# 5_MOTORES_DE_PASSO.net
KiCad netlist of a schematic drawn in Altium Designer
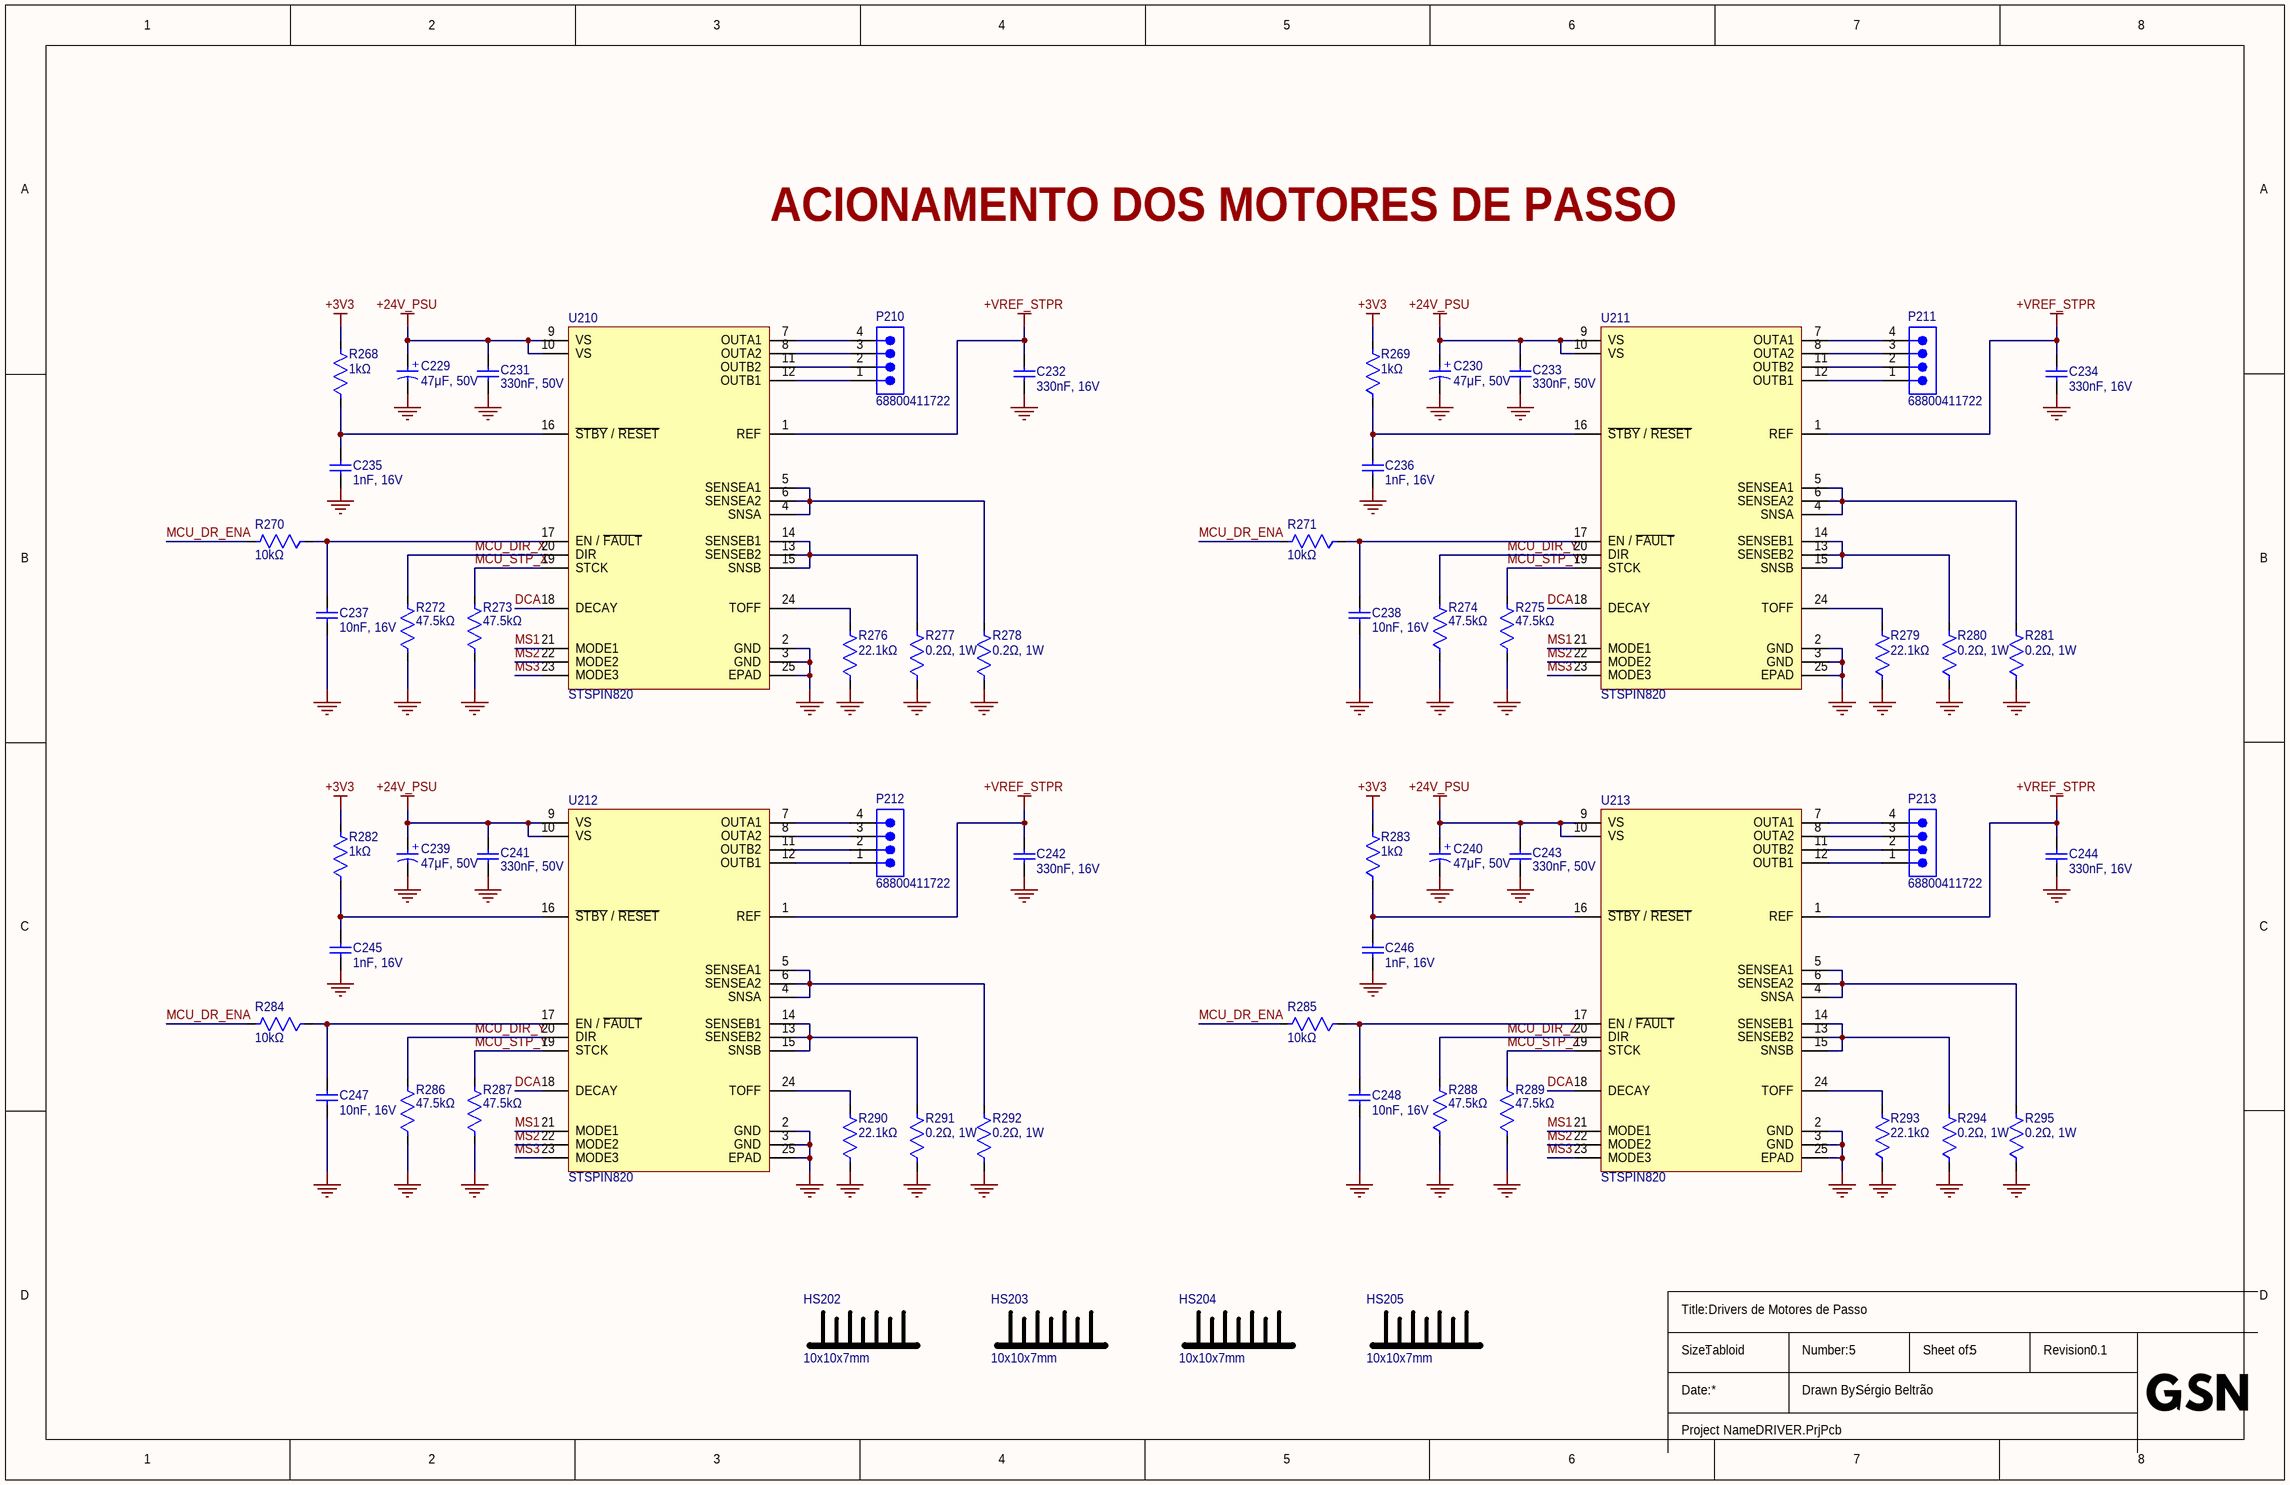
[diagram p0: 5_MOTORES_DE_PASSO.SchDoc]

(export (version "E")
  (design (tool "Eeschema 10.0.6"))
  (components
    (comp (ref "C229")
      (value "47μF, 50V")
      (footprint "WCAP-ASLI_D6.3H7.7")
      (description "WCAP-ASLI Aluminum Electrolytic Capacitor, V-Chip, SMT, 6.3mm x 7.7mm, 47μF, 50V")
      (fields
        (field (name "MANUFACTURER PART NUMBER") "865080645012")
        (field (name "MANUFACTURER") "Wurth Elektronik")
      )
      (libsource (lib "WE - Passive Components") (part "Capacitor_Polarized"))
    )
    (comp (ref "C230")
      (value "47μF, 50V")
      (footprint "WCAP-ASLI_D6.3H7.7")
      (description "WCAP-ASLI Aluminum Electrolytic Capacitor, V-Chip, SMT, 6.3mm x 7.7mm, 47μF, 50V")
      (fields
        (field (name "MANUFACTURER PART NUMBER") "865080645012")
        (field (name "MANUFACTURER") "Wurth Elektronik")
      )
      (libsource (lib "WE - Passive Components") (part "Capacitor_Polarized"))
    )
    (comp (ref "C231")
      (value "330nF, 50V")
      (footprint "WCAP-CSGP_0603_L1.6W0.8H0.8_Wave")
      (description "WCAP-CSGP Multilayer Ceramic Chip Capacitor, General Purpose, size 0603, 330nF, 50V")
      (fields
        (field (name "MANUFACTURER PART NUMBER") "885012206121")
        (field (name "MANUFACTURER") "Wurth Elektronik")
      )
      (libsource (lib "WE - Passive Components") (part "Capacitor_Non-Polarized"))
    )
    (comp (ref "C232")
      (value "330nF, 16V")
      (footprint "WCAP-CSGP_0603_L1.6W0.8H0.8_Wave")
      (description "WCAP-CSGP Multilayer Ceramic Chip Capacitor, General Purpose, size 0603, 330nF, 16V")
      (fields
        (field (name "MANUFACTURER PART NUMBER") "885012206049")
        (field (name "MANUFACTURER") "Wurth Elektronik")
      )
      (libsource (lib "WE - Passive Components") (part "Capacitor_Non-Polarized"))
    )
    (comp (ref "C233")
      (value "330nF, 50V")
      (footprint "WCAP-CSGP_0603_L1.6W0.8H0.8_Wave")
      (description "WCAP-CSGP Multilayer Ceramic Chip Capacitor, General Purpose, size 0603, 330nF, 50V")
      (fields
        (field (name "MANUFACTURER PART NUMBER") "885012206121")
        (field (name "MANUFACTURER") "Wurth Elektronik")
      )
      (libsource (lib "WE - Passive Components") (part "Capacitor_Non-Polarized"))
    )
    (comp (ref "C234")
      (value "330nF, 16V")
      (footprint "WCAP-CSGP_0603_L1.6W0.8H0.8_Wave")
      (description "WCAP-CSGP Multilayer Ceramic Chip Capacitor, General Purpose, size 0603, 330nF, 16V")
      (fields
        (field (name "MANUFACTURER PART NUMBER") "885012206049")
        (field (name "MANUFACTURER") "Wurth Elektronik")
      )
      (libsource (lib "WE - Passive Components") (part "Capacitor_Non-Polarized"))
    )
    (comp (ref "C235")
      (value "1nF, 16V")
      (footprint "WCAP-CSGP_0603_L1.6W0.8H0.8_Wave")
      (description "WCAP-CSGP Multilayer Ceramic Chip Capacitor, General Purpose, size 0603, 1nF, 16V")
      (fields
        (field (name "MANUFACTURER PART NUMBER") "885012206034")
        (field (name "MANUFACTURER") "Wurth Elektronik")
      )
      (libsource (lib "WE - Passive Components") (part "Capacitor_Non-Polarized"))
    )
    (comp (ref "C236")
      (value "1nF, 16V")
      (footprint "WCAP-CSGP_0603_L1.6W0.8H0.8_Wave")
      (description "WCAP-CSGP Multilayer Ceramic Chip Capacitor, General Purpose, size 0603, 1nF, 16V")
      (fields
        (field (name "MANUFACTURER PART NUMBER") "885012206034")
        (field (name "MANUFACTURER") "Wurth Elektronik")
      )
      (libsource (lib "WE - Passive Components") (part "Capacitor_Non-Polarized"))
    )
    (comp (ref "C237")
      (value "10nF, 16V")
      (footprint "WCAP-CSGP_0603_L1.6W0.8H0.8_Wave")
      (description "WCAP-CSGP Multilayer Ceramic Chip Capacitor, General Purpose, size 0603, 10nF, 16V")
      (fields
        (field (name "MANUFACTURER PART NUMBER") "885012206040")
        (field (name "MANUFACTURER") "Wurth Elektronik")
      )
      (libsource (lib "WE - Passive Components") (part "Capacitor_Non-Polarized"))
    )
    (comp (ref "C238")
      (value "10nF, 16V")
      (footprint "WCAP-CSGP_0603_L1.6W0.8H0.8_Wave")
      (description "WCAP-CSGP Multilayer Ceramic Chip Capacitor, General Purpose, size 0603, 10nF, 16V")
      (fields
        (field (name "MANUFACTURER PART NUMBER") "885012206040")
        (field (name "MANUFACTURER") "Wurth Elektronik")
      )
      (libsource (lib "WE - Passive Components") (part "Capacitor_Non-Polarized"))
    )
    (comp (ref "C239")
      (value "47μF, 50V")
      (footprint "WCAP-ASLI_D6.3H7.7")
      (description "WCAP-ASLI Aluminum Electrolytic Capacitor, V-Chip, SMT, 6.3mm x 7.7mm, 47μF, 50V")
      (fields
        (field (name "MANUFACTURER PART NUMBER") "865080645012")
        (field (name "MANUFACTURER") "Wurth Elektronik")
      )
      (libsource (lib "WE - Passive Components") (part "Capacitor_Polarized"))
    )
    (comp (ref "C240")
      (value "47μF, 50V")
      (footprint "WCAP-ASLI_D6.3H7.7")
      (description "WCAP-ASLI Aluminum Electrolytic Capacitor, V-Chip, SMT, 6.3mm x 7.7mm, 47μF, 50V")
      (fields
        (field (name "MANUFACTURER PART NUMBER") "865080645012")
        (field (name "MANUFACTURER") "Wurth Elektronik")
      )
      (libsource (lib "WE - Passive Components") (part "Capacitor_Polarized"))
    )
    (comp (ref "C241")
      (value "330nF, 50V")
      (footprint "WCAP-CSGP_0603_L1.6W0.8H0.8_Wave")
      (description "WCAP-CSGP Multilayer Ceramic Chip Capacitor, General Purpose, size 0603, 330nF, 50V")
      (fields
        (field (name "MANUFACTURER PART NUMBER") "885012206121")
        (field (name "MANUFACTURER") "Wurth Elektronik")
      )
      (libsource (lib "WE - Passive Components") (part "Capacitor_Non-Polarized"))
    )
    (comp (ref "C242")
      (value "330nF, 16V")
      (footprint "WCAP-CSGP_0603_L1.6W0.8H0.8_Wave")
      (description "WCAP-CSGP Multilayer Ceramic Chip Capacitor, General Purpose, size 0603, 330nF, 16V")
      (fields
        (field (name "MANUFACTURER PART NUMBER") "885012206049")
        (field (name "MANUFACTURER") "Wurth Elektronik")
      )
      (libsource (lib "WE - Passive Components") (part "Capacitor_Non-Polarized"))
    )
    (comp (ref "C243")
      (value "330nF, 50V")
      (footprint "WCAP-CSGP_0603_L1.6W0.8H0.8_Wave")
      (description "WCAP-CSGP Multilayer Ceramic Chip Capacitor, General Purpose, size 0603, 330nF, 50V")
      (fields
        (field (name "MANUFACTURER PART NUMBER") "885012206121")
        (field (name "MANUFACTURER") "Wurth Elektronik")
      )
      (libsource (lib "WE - Passive Components") (part "Capacitor_Non-Polarized"))
    )
    (comp (ref "C244")
      (value "330nF, 16V")
      (footprint "WCAP-CSGP_0603_L1.6W0.8H0.8_Wave")
      (description "WCAP-CSGP Multilayer Ceramic Chip Capacitor, General Purpose, size 0603, 330nF, 16V")
      (fields
        (field (name "MANUFACTURER PART NUMBER") "885012206049")
        (field (name "MANUFACTURER") "Wurth Elektronik")
      )
      (libsource (lib "WE - Passive Components") (part "Capacitor_Non-Polarized"))
    )
    (comp (ref "C245")
      (value "1nF, 16V")
      (footprint "WCAP-CSGP_0603_L1.6W0.8H0.8_Wave")
      (description "WCAP-CSGP Multilayer Ceramic Chip Capacitor, General Purpose, size 0603, 1nF, 16V")
      (fields
        (field (name "MANUFACTURER PART NUMBER") "885012206034")
        (field (name "MANUFACTURER") "Wurth Elektronik")
      )
      (libsource (lib "WE - Passive Components") (part "Capacitor_Non-Polarized"))
    )
    (comp (ref "C246")
      (value "1nF, 16V")
      (footprint "WCAP-CSGP_0603_L1.6W0.8H0.8_Wave")
      (description "WCAP-CSGP Multilayer Ceramic Chip Capacitor, General Purpose, size 0603, 1nF, 16V")
      (fields
        (field (name "MANUFACTURER PART NUMBER") "885012206034")
        (field (name "MANUFACTURER") "Wurth Elektronik")
      )
      (libsource (lib "WE - Passive Components") (part "Capacitor_Non-Polarized"))
    )
    (comp (ref "C247")
      (value "10nF, 16V")
      (footprint "WCAP-CSGP_0603_L1.6W0.8H0.8_Wave")
      (description "WCAP-CSGP Multilayer Ceramic Chip Capacitor, General Purpose, size 0603, 10nF, 16V")
      (fields
        (field (name "MANUFACTURER PART NUMBER") "885012206040")
        (field (name "MANUFACTURER") "Wurth Elektronik")
      )
      (libsource (lib "WE - Passive Components") (part "Capacitor_Non-Polarized"))
    )
    (comp (ref "C248")
      (value "10nF, 16V")
      (footprint "WCAP-CSGP_0603_L1.6W0.8H0.8_Wave")
      (description "WCAP-CSGP Multilayer Ceramic Chip Capacitor, General Purpose, size 0603, 10nF, 16V")
      (fields
        (field (name "MANUFACTURER PART NUMBER") "885012206040")
        (field (name "MANUFACTURER") "Wurth Elektronik")
      )
      (libsource (lib "WE - Passive Components") (part "Capacitor_Non-Polarized"))
    )
    (comp (ref "HS202")
      (value "10x10x7mm")
      (footprint "HEATSINK_10MM_10MM_7MM")
      (description "GENERIC HEATSINK 10X10X7MM")
      (fields (field (name "MANUFACTURER") "OEM") (field (name "MANUFACTURER PART NUMBER") "None"))
      (libsource (lib "Electro-Mechanical") (part "GENERIC-HEATSINK-10X10X7MM"))
    )
    (comp (ref "HS203")
      (value "10x10x7mm")
      (footprint "HEATSINK_10MM_10MM_7MM")
      (description "GENERIC HEATSINK 10X10X7MM")
      (fields (field (name "MANUFACTURER") "OEM") (field (name "MANUFACTURER PART NUMBER") "None"))
      (libsource (lib "Electro-Mechanical") (part "GENERIC-HEATSINK-10X10X7MM"))
    )
    (comp (ref "HS204")
      (value "10x10x7mm")
      (footprint "HEATSINK_10MM_10MM_7MM")
      (description "GENERIC HEATSINK 10X10X7MM")
      (fields (field (name "MANUFACTURER") "OEM") (field (name "MANUFACTURER PART NUMBER") "None"))
      (libsource (lib "Electro-Mechanical") (part "GENERIC-HEATSINK-10X10X7MM"))
    )
    (comp (ref "HS205")
      (value "10x10x7mm")
      (footprint "HEATSINK_10MM_10MM_7MM")
      (description "GENERIC HEATSINK 10X10X7MM")
      (fields (field (name "MANUFACTURER") "OEM") (field (name "MANUFACTURER PART NUMBER") "None"))
      (libsource (lib "Electro-Mechanical") (part "GENERIC-HEATSINK-10X10X7MM"))
    )
    (comp (ref "P210")
      (value "68800411722")
      (footprint "68800411722")
      (description "WR-WTB “J” Type THT Male Horizontal Shrouded Header, pitch 2.5 mm, 4 pins")
      (fields (field (name "MANUFACTURER") "Wurth Elektronik"))
      (libsource (lib "WE - Electromechanical Components") (part "Header_Male_1R_04P"))
    )
    (comp (ref "P211")
      (value "68800411722")
      (footprint "68800411722")
      (description "WR-WTB “J” Type THT Male Horizontal Shrouded Header, pitch 2.5 mm, 4 pins")
      (fields (field (name "MANUFACTURER") "Wurth Elektronik"))
      (libsource (lib "WE - Electromechanical Components") (part "Header_Male_1R_04P"))
    )
    (comp (ref "P212")
      (value "68800411722")
      (footprint "68800411722")
      (description "WR-WTB “J” Type THT Male Horizontal Shrouded Header, pitch 2.5 mm, 4 pins")
      (fields (field (name "MANUFACTURER") "Wurth Elektronik"))
      (libsource (lib "WE - Electromechanical Components") (part "Header_Male_1R_04P"))
    )
    (comp (ref "P213")
      (value "68800411722")
      (footprint "68800411722")
      (description "WR-WTB “J” Type THT Male Horizontal Shrouded Header, pitch 2.5 mm, 4 pins")
      (fields (field (name "MANUFACTURER") "Wurth Elektronik"))
      (libsource (lib "WE - Electromechanical Components") (part "Header_Male_1R_04P"))
    )
    (comp (ref "R268")
      (value "1kΩ")
      (footprint "0603-WAVE")
      (description "RES 1K OHM 1% 1/10W 0603")
      (fields
        (field (name "MANUFACTURER PART NUMBER") "RC0603FR-071KL")
        (field (name "MANUFACTURER") "Yageo Group")
      )
      (libsource (lib "Resistors-0603-E96-Yageo") (part "RC0603FR-071KL"))
    )
    (comp (ref "R269")
      (value "1kΩ")
      (footprint "0603-WAVE")
      (description "RES 1K OHM 1% 1/10W 0603")
      (fields
        (field (name "MANUFACTURER PART NUMBER") "RC0603FR-071KL")
        (field (name "MANUFACTURER") "Yageo Group")
      )
      (libsource (lib "Resistors-0603-E96-Yageo") (part "RC0603FR-071KL"))
    )
    (comp (ref "R270")
      (value "10kΩ")
      (footprint "0603-WAVE")
      (description "RES 10K OHM 1% 1/10W 0603")
      (fields
        (field (name "MANUFACTURER PART NUMBER") "RC0603FR-0710KL")
        (field (name "MANUFACTURER") "Yageo Group")
      )
      (libsource (lib "Resistors-0603-E96-Yageo") (part "RC0603FR-0710KL"))
    )
    (comp (ref "R271")
      (value "10kΩ")
      (footprint "0603-WAVE")
      (description "RES 10K OHM 1% 1/10W 0603")
      (fields
        (field (name "MANUFACTURER PART NUMBER") "RC0603FR-0710KL")
        (field (name "MANUFACTURER") "Yageo Group")
      )
      (libsource (lib "Resistors-0603-E96-Yageo") (part "RC0603FR-0710KL"))
    )
    (comp (ref "R272")
      (value "47.5kΩ")
      (footprint "0603-WAVE")
      (description "RES 47.5K OHM 1% 1/10W 0603")
      (fields
        (field (name "MANUFACTURER PART NUMBER") "RC0603FR-0747K5L")
        (field (name "MANUFACTURER") "Yageo Group")
      )
      (libsource (lib "Resistors-0603-E96-Yageo") (part "RC0603FR-0747K5L"))
    )
    (comp (ref "R273")
      (value "47.5kΩ")
      (footprint "0603-WAVE")
      (description "RES 47.5K OHM 1% 1/10W 0603")
      (fields
        (field (name "MANUFACTURER PART NUMBER") "RC0603FR-0747K5L")
        (field (name "MANUFACTURER") "Yageo Group")
      )
      (libsource (lib "Resistors-0603-E96-Yageo") (part "RC0603FR-0747K5L"))
    )
    (comp (ref "R274")
      (value "47.5kΩ")
      (footprint "0603-WAVE")
      (description "RES 47.5K OHM 1% 1/10W 0603")
      (fields
        (field (name "MANUFACTURER PART NUMBER") "RC0603FR-0747K5L")
        (field (name "MANUFACTURER") "Yageo Group")
      )
      (libsource (lib "Resistors-0603-E96-Yageo") (part "RC0603FR-0747K5L"))
    )
    (comp (ref "R275")
      (value "47.5kΩ")
      (footprint "0603-WAVE")
      (description "RES 47.5K OHM 1% 1/10W 0603")
      (fields
        (field (name "MANUFACTURER PART NUMBER") "RC0603FR-0747K5L")
        (field (name "MANUFACTURER") "Yageo Group")
      )
      (libsource (lib "Resistors-0603-E96-Yageo") (part "RC0603FR-0747K5L"))
    )
    (comp (ref "R276")
      (value "22.1kΩ")
      (footprint "0603-WAVE")
      (description "RES 22.1K OHM 1% 1/10W 0603")
      (fields
        (field (name "MANUFACTURER PART NUMBER") "RC0603FR-0722K1L")
        (field (name "MANUFACTURER") "Yageo Group")
      )
      (libsource (lib "Resistors-0603-E96-Yageo") (part "RC0603FR-0722K1L"))
    )
    (comp (ref "R277")
      (value "0.2Ω, 1W")
      (footprint "2512-WAVE")
      (description "RES 0.2 OHM 1% 1W 2512")
      (fields
        (field (name "MANUFACTURER") "Yageo Group")
        (field (name "MANUFACTURER PART NUMBER") "RL2512FK-070R2L")
      )
      (libsource (lib "Resistors-2512-Shunt") (part "RL2512FK-070R2L"))
    )
    (comp (ref "R278")
      (value "0.2Ω, 1W")
      (footprint "2512-WAVE")
      (description "RES 0.2 OHM 1% 1W 2512")
      (fields
        (field (name "MANUFACTURER") "Yageo Group")
        (field (name "MANUFACTURER PART NUMBER") "RL2512FK-070R2L")
      )
      (libsource (lib "Resistors-2512-Shunt") (part "RL2512FK-070R2L"))
    )
    (comp (ref "R279")
      (value "22.1kΩ")
      (footprint "0603-WAVE")
      (description "RES 22.1K OHM 1% 1/10W 0603")
      (fields
        (field (name "MANUFACTURER PART NUMBER") "RC0603FR-0722K1L")
        (field (name "MANUFACTURER") "Yageo Group")
      )
      (libsource (lib "Resistors-0603-E96-Yageo") (part "RC0603FR-0722K1L"))
    )
    (comp (ref "R280")
      (value "0.2Ω, 1W")
      (footprint "2512-WAVE")
      (description "RES 0.2 OHM 1% 1W 2512")
      (fields
        (field (name "MANUFACTURER") "Yageo Group")
        (field (name "MANUFACTURER PART NUMBER") "RL2512FK-070R2L")
      )
      (libsource (lib "Resistors-2512-Shunt") (part "RL2512FK-070R2L"))
    )
    (comp (ref "R281")
      (value "0.2Ω, 1W")
      (footprint "2512-WAVE")
      (description "RES 0.2 OHM 1% 1W 2512")
      (fields
        (field (name "MANUFACTURER") "Yageo Group")
        (field (name "MANUFACTURER PART NUMBER") "RL2512FK-070R2L")
      )
      (libsource (lib "Resistors-2512-Shunt") (part "RL2512FK-070R2L"))
    )
    (comp (ref "R282")
      (value "1kΩ")
      (footprint "0603-WAVE")
      (description "RES 1K OHM 1% 1/10W 0603")
      (fields
        (field (name "MANUFACTURER PART NUMBER") "RC0603FR-071KL")
        (field (name "MANUFACTURER") "Yageo Group")
      )
      (libsource (lib "Resistors-0603-E96-Yageo") (part "RC0603FR-071KL"))
    )
    (comp (ref "R283")
      (value "1kΩ")
      (footprint "0603-WAVE")
      (description "RES 1K OHM 1% 1/10W 0603")
      (fields
        (field (name "MANUFACTURER PART NUMBER") "RC0603FR-071KL")
        (field (name "MANUFACTURER") "Yageo Group")
      )
      (libsource (lib "Resistors-0603-E96-Yageo") (part "RC0603FR-071KL"))
    )
    (comp (ref "R284")
      (value "10kΩ")
      (footprint "0603-WAVE")
      (description "RES 10K OHM 1% 1/10W 0603")
      (fields
        (field (name "MANUFACTURER PART NUMBER") "RC0603FR-0710KL")
        (field (name "MANUFACTURER") "Yageo Group")
      )
      (libsource (lib "Resistors-0603-E96-Yageo") (part "RC0603FR-0710KL"))
    )
    (comp (ref "R285")
      (value "10kΩ")
      (footprint "0603-WAVE")
      (description "RES 10K OHM 1% 1/10W 0603")
      (fields
        (field (name "MANUFACTURER PART NUMBER") "RC0603FR-0710KL")
        (field (name "MANUFACTURER") "Yageo Group")
      )
      (libsource (lib "Resistors-0603-E96-Yageo") (part "RC0603FR-0710KL"))
    )
    (comp (ref "R286")
      (value "47.5kΩ")
      (footprint "0603-WAVE")
      (description "RES 47.5K OHM 1% 1/10W 0603")
      (fields
        (field (name "MANUFACTURER PART NUMBER") "RC0603FR-0747K5L")
        (field (name "MANUFACTURER") "Yageo Group")
      )
      (libsource (lib "Resistors-0603-E96-Yageo") (part "RC0603FR-0747K5L"))
    )
    (comp (ref "R287")
      (value "47.5kΩ")
      (footprint "0603-WAVE")
      (description "RES 47.5K OHM 1% 1/10W 0603")
      (fields
        (field (name "MANUFACTURER PART NUMBER") "RC0603FR-0747K5L")
        (field (name "MANUFACTURER") "Yageo Group")
      )
      (libsource (lib "Resistors-0603-E96-Yageo") (part "RC0603FR-0747K5L"))
    )
    (comp (ref "R288")
      (value "47.5kΩ")
      (footprint "0603-WAVE")
      (description "RES 47.5K OHM 1% 1/10W 0603")
      (fields
        (field (name "MANUFACTURER PART NUMBER") "RC0603FR-0747K5L")
        (field (name "MANUFACTURER") "Yageo Group")
      )
      (libsource (lib "Resistors-0603-E96-Yageo") (part "RC0603FR-0747K5L"))
    )
    (comp (ref "R289")
      (value "47.5kΩ")
      (footprint "0603-WAVE")
      (description "RES 47.5K OHM 1% 1/10W 0603")
      (fields
        (field (name "MANUFACTURER PART NUMBER") "RC0603FR-0747K5L")
        (field (name "MANUFACTURER") "Yageo Group")
      )
      (libsource (lib "Resistors-0603-E96-Yageo") (part "RC0603FR-0747K5L"))
    )
    (comp (ref "R290")
      (value "22.1kΩ")
      (footprint "0603-WAVE")
      (description "RES 22.1K OHM 1% 1/10W 0603")
      (fields
        (field (name "MANUFACTURER PART NUMBER") "RC0603FR-0722K1L")
        (field (name "MANUFACTURER") "Yageo Group")
      )
      (libsource (lib "Resistors-0603-E96-Yageo") (part "RC0603FR-0722K1L"))
    )
    (comp (ref "R291")
      (value "0.2Ω, 1W")
      (footprint "2512-WAVE")
      (description "RES 0.2 OHM 1% 1W 2512")
      (fields
        (field (name "MANUFACTURER") "Yageo Group")
        (field (name "MANUFACTURER PART NUMBER") "RL2512FK-070R2L")
      )
      (libsource (lib "Resistors-2512-Shunt") (part "RL2512FK-070R2L"))
    )
    (comp (ref "R292")
      (value "0.2Ω, 1W")
      (footprint "2512-WAVE")
      (description "RES 0.2 OHM 1% 1W 2512")
      (fields
        (field (name "MANUFACTURER") "Yageo Group")
        (field (name "MANUFACTURER PART NUMBER") "RL2512FK-070R2L")
      )
      (libsource (lib "Resistors-2512-Shunt") (part "RL2512FK-070R2L"))
    )
    (comp (ref "R293")
      (value "22.1kΩ")
      (footprint "0603-WAVE")
      (description "RES 22.1K OHM 1% 1/10W 0603")
      (fields
        (field (name "MANUFACTURER PART NUMBER") "RC0603FR-0722K1L")
        (field (name "MANUFACTURER") "Yageo Group")
      )
      (libsource (lib "Resistors-0603-E96-Yageo") (part "RC0603FR-0722K1L"))
    )
    (comp (ref "R294")
      (value "0.2Ω, 1W")
      (footprint "2512-WAVE")
      (description "RES 0.2 OHM 1% 1W 2512")
      (fields
        (field (name "MANUFACTURER") "Yageo Group")
        (field (name "MANUFACTURER PART NUMBER") "RL2512FK-070R2L")
      )
      (libsource (lib "Resistors-2512-Shunt") (part "RL2512FK-070R2L"))
    )
    (comp (ref "R295")
      (value "0.2Ω, 1W")
      (footprint "2512-WAVE")
      (description "RES 0.2 OHM 1% 1W 2512")
      (fields
        (field (name "MANUFACTURER") "Yageo Group")
        (field (name "MANUFACTURER PART NUMBER") "RL2512FK-070R2L")
      )
      (libsource (lib "Resistors-2512-Shunt") (part "RL2512FK-070R2L"))
    )
    (comp (ref "U210")
      (value "STSPIN820")
      (footprint "24-TQFPN")
      (description "IC MTR DRVR BIPLR 7-45V 24TFQFPN")
      (fields (field (name "MANUFACTURER") "STMicroelectronics"))
      (libsource (lib "Motor-Drivers") (part "STSPIN820"))
    )
    (comp (ref "U211")
      (value "STSPIN820")
      (footprint "24-TQFPN")
      (description "IC MTR DRVR BIPLR 7-45V 24TFQFPN")
      (fields (field (name "MANUFACTURER") "STMicroelectronics"))
      (libsource (lib "Motor-Drivers") (part "STSPIN820"))
    )
    (comp (ref "U212")
      (value "STSPIN820")
      (footprint "24-TQFPN")
      (description "IC MTR DRVR BIPLR 7-45V 24TFQFPN")
      (fields (field (name "MANUFACTURER") "STMicroelectronics"))
      (libsource (lib "Motor-Drivers") (part "STSPIN820"))
    )
    (comp (ref "U213")
      (value "STSPIN820")
      (footprint "24-TQFPN")
      (description "IC MTR DRVR BIPLR 7-45V 24TFQFPN")
      (fields (field (name "MANUFACTURER") "STMicroelectronics"))
      (libsource (lib "Motor-Drivers") (part "STSPIN820"))
    )
  )
  (nets
    (net (code "1") (name "+3V3") (class "Default")
      (node (ref "R268") (pin "2") (pinfunction "2_2") (pintype "passive"))
      (node (ref "R269") (pin "2") (pinfunction "2_2") (pintype "passive"))
      (node (ref "R282") (pin "2") (pinfunction "2_2") (pintype "passive"))
      (node (ref "R283") (pin "2") (pinfunction "2_2") (pintype "passive"))
    )
    (net (code "2") (name "+24V_PSU") (class "Default")
      (node (ref "C229") (pin "1") (pinfunction "P_1") (pintype "passive"))
      (node (ref "C230") (pin "1") (pinfunction "P_1") (pintype "passive"))
      (node (ref "C231") (pin "2") (pinfunction "2_2") (pintype "passive"))
      (node (ref "C233") (pin "2") (pinfunction "2_2") (pintype "passive"))
      (node (ref "C239") (pin "1") (pinfunction "P_1") (pintype "passive"))
      (node (ref "C240") (pin "1") (pinfunction "P_1") (pintype "passive"))
      (node (ref "C241") (pin "2") (pinfunction "2_2") (pintype "passive"))
      (node (ref "C243") (pin "2") (pinfunction "2_2") (pintype "passive"))
      (node (ref "U210") (pin "10") (pinfunction "VS_10") (pintype "passive"))
      (node (ref "U210") (pin "9") (pinfunction "VS_9") (pintype "passive"))
      (node (ref "U211") (pin "10") (pinfunction "VS_10") (pintype "passive"))
      (node (ref "U211") (pin "9") (pinfunction "VS_9") (pintype "passive"))
      (node (ref "U212") (pin "10") (pinfunction "VS_10") (pintype "passive"))
      (node (ref "U212") (pin "9") (pinfunction "VS_9") (pintype "passive"))
      (node (ref "U213") (pin "10") (pinfunction "VS_10") (pintype "passive"))
      (node (ref "U213") (pin "9") (pinfunction "VS_9") (pintype "passive"))
    )
    (net (code "3") (name "+VREF_STPR") (class "Default")
      (node (ref "C232") (pin "2") (pinfunction "2_2") (pintype "passive"))
      (node (ref "C234") (pin "2") (pinfunction "2_2") (pintype "passive"))
      (node (ref "C242") (pin "2") (pinfunction "2_2") (pintype "passive"))
      (node (ref "C244") (pin "2") (pinfunction "2_2") (pintype "passive"))
      (node (ref "U210") (pin "1") (pinfunction "REF_1") (pintype "passive"))
      (node (ref "U211") (pin "1") (pinfunction "REF_1") (pintype "passive"))
      (node (ref "U212") (pin "1") (pinfunction "REF_1") (pintype "passive"))
      (node (ref "U213") (pin "1") (pinfunction "REF_1") (pintype "passive"))
    )
    (net (code "4") (name "/DCA") (class "Default")
      (node (ref "U210") (pin "18") (pinfunction "DECAY_18") (pintype "passive"))
      (node (ref "U211") (pin "18") (pinfunction "DECAY_18") (pintype "passive"))
      (node (ref "U212") (pin "18") (pinfunction "DECAY_18") (pintype "passive"))
      (node (ref "U213") (pin "18") (pinfunction "DECAY_18") (pintype "passive"))
    )
    (net (code "5") (name "/MCU_DIR_X") (class "Default")
      (node (ref "R272") (pin "2") (pinfunction "2_2") (pintype "passive"))
      (node (ref "U210") (pin "20") (pinfunction "DIR_20") (pintype "passive"))
    )
    (net (code "6") (name "/MCU_DIR_Y") (class "Default")
      (node (ref "R274") (pin "2") (pinfunction "2_2") (pintype "passive"))
      (node (ref "R286") (pin "2") (pinfunction "2_2") (pintype "passive"))
      (node (ref "U211") (pin "20") (pinfunction "DIR_20") (pintype "passive"))
      (node (ref "U212") (pin "20") (pinfunction "DIR_20") (pintype "passive"))
    )
    (net (code "7") (name "/MCU_DIR_Z") (class "Default")
      (node (ref "R288") (pin "2") (pinfunction "2_2") (pintype "passive"))
      (node (ref "U213") (pin "20") (pinfunction "DIR_20") (pintype "passive"))
    )
    (net (code "8") (name "/MCU_DR_ENA") (class "Default")
      (node (ref "R270") (pin "2") (pinfunction "2_2") (pintype "passive"))
      (node (ref "R271") (pin "2") (pinfunction "2_2") (pintype "passive"))
      (node (ref "R284") (pin "2") (pinfunction "2_2") (pintype "passive"))
      (node (ref "R285") (pin "2") (pinfunction "2_2") (pintype "passive"))
    )
    (net (code "9") (name "/MCU_STP_X") (class "Default")
      (node (ref "R273") (pin "2") (pinfunction "2_2") (pintype "passive"))
      (node (ref "U210") (pin "19") (pinfunction "STCK_19") (pintype "passive"))
    )
    (net (code "10") (name "/MCU_STP_Y") (class "Default")
      (node (ref "R275") (pin "2") (pinfunction "2_2") (pintype "passive"))
      (node (ref "R287") (pin "2") (pinfunction "2_2") (pintype "passive"))
      (node (ref "U211") (pin "19") (pinfunction "STCK_19") (pintype "passive"))
      (node (ref "U212") (pin "19") (pinfunction "STCK_19") (pintype "passive"))
    )
    (net (code "11") (name "/MCU_STP_Z") (class "Default")
      (node (ref "R289") (pin "2") (pinfunction "2_2") (pintype "passive"))
      (node (ref "U213") (pin "19") (pinfunction "STCK_19") (pintype "passive"))
    )
    (net (code "12") (name "/MS1") (class "Default")
      (node (ref "U210") (pin "21") (pinfunction "MODE1_21") (pintype "passive"))
      (node (ref "U211") (pin "21") (pinfunction "MODE1_21") (pintype "passive"))
      (node (ref "U212") (pin "21") (pinfunction "MODE1_21") (pintype "passive"))
      (node (ref "U213") (pin "21") (pinfunction "MODE1_21") (pintype "passive"))
    )
    (net (code "13") (name "/MS2") (class "Default")
      (node (ref "U210") (pin "22") (pinfunction "MODE2_22") (pintype "passive"))
      (node (ref "U211") (pin "22") (pinfunction "MODE2_22") (pintype "passive"))
      (node (ref "U212") (pin "22") (pinfunction "MODE2_22") (pintype "passive"))
      (node (ref "U213") (pin "22") (pinfunction "MODE2_22") (pintype "passive"))
    )
    (net (code "14") (name "/MS3") (class "Default")
      (node (ref "U210") (pin "23") (pinfunction "MODE3_23") (pintype "passive"))
      (node (ref "U211") (pin "23") (pinfunction "MODE3_23") (pintype "passive"))
      (node (ref "U212") (pin "23") (pinfunction "MODE3_23") (pintype "passive"))
      (node (ref "U213") (pin "23") (pinfunction "MODE3_23") (pintype "passive"))
    )
    (net (code "15") (name "GND") (class "Default")
      (node (ref "C229") (pin "2") (pinfunction "N_2") (pintype "passive"))
      (node (ref "C230") (pin "2") (pinfunction "N_2") (pintype "passive"))
      (node (ref "C231") (pin "1") (pinfunction "1_1") (pintype "passive"))
      (node (ref "C232") (pin "1") (pinfunction "1_1") (pintype "passive"))
      (node (ref "C233") (pin "1") (pinfunction "1_1") (pintype "passive"))
      (node (ref "C234") (pin "1") (pinfunction "1_1") (pintype "passive"))
      (node (ref "C235") (pin "1") (pinfunction "1_1") (pintype "passive"))
      (node (ref "C236") (pin "1") (pinfunction "1_1") (pintype "passive"))
      (node (ref "C237") (pin "1") (pinfunction "1_1") (pintype "passive"))
      (node (ref "C238") (pin "1") (pinfunction "1_1") (pintype "passive"))
      (node (ref "C239") (pin "2") (pinfunction "N_2") (pintype "passive"))
      (node (ref "C240") (pin "2") (pinfunction "N_2") (pintype "passive"))
      (node (ref "C241") (pin "1") (pinfunction "1_1") (pintype "passive"))
      (node (ref "C242") (pin "1") (pinfunction "1_1") (pintype "passive"))
      (node (ref "C243") (pin "1") (pinfunction "1_1") (pintype "passive"))
      (node (ref "C244") (pin "1") (pinfunction "1_1") (pintype "passive"))
      (node (ref "C245") (pin "1") (pinfunction "1_1") (pintype "passive"))
      (node (ref "C246") (pin "1") (pinfunction "1_1") (pintype "passive"))
      (node (ref "C247") (pin "1") (pinfunction "1_1") (pintype "passive"))
      (node (ref "C248") (pin "1") (pinfunction "1_1") (pintype "passive"))
      (node (ref "R272") (pin "1") (pinfunction "1_1") (pintype "passive"))
      (node (ref "R273") (pin "1") (pinfunction "1_1") (pintype "passive"))
      (node (ref "R274") (pin "1") (pinfunction "1_1") (pintype "passive"))
      (node (ref "R275") (pin "1") (pinfunction "1_1") (pintype "passive"))
      (node (ref "R276") (pin "1") (pinfunction "1_1") (pintype "passive"))
      (node (ref "R277") (pin "1") (pinfunction "1_1") (pintype "passive"))
      (node (ref "R278") (pin "1") (pinfunction "1_1") (pintype "passive"))
      (node (ref "R279") (pin "1") (pinfunction "1_1") (pintype "passive"))
      (node (ref "R280") (pin "1") (pinfunction "1_1") (pintype "passive"))
      (node (ref "R281") (pin "1") (pinfunction "1_1") (pintype "passive"))
      (node (ref "R286") (pin "1") (pinfunction "1_1") (pintype "passive"))
      (node (ref "R287") (pin "1") (pinfunction "1_1") (pintype "passive"))
      (node (ref "R288") (pin "1") (pinfunction "1_1") (pintype "passive"))
      (node (ref "R289") (pin "1") (pinfunction "1_1") (pintype "passive"))
      (node (ref "R290") (pin "1") (pinfunction "1_1") (pintype "passive"))
      (node (ref "R291") (pin "1") (pinfunction "1_1") (pintype "passive"))
      (node (ref "R292") (pin "1") (pinfunction "1_1") (pintype "passive"))
      (node (ref "R293") (pin "1") (pinfunction "1_1") (pintype "passive"))
      (node (ref "R294") (pin "1") (pinfunction "1_1") (pintype "passive"))
      (node (ref "R295") (pin "1") (pinfunction "1_1") (pintype "passive"))
      (node (ref "U210") (pin "2") (pinfunction "GND_2") (pintype "passive"))
      (node (ref "U210") (pin "25") (pinfunction "EPAD_25") (pintype "passive"))
      (node (ref "U210") (pin "3") (pinfunction "GND_3") (pintype "passive"))
      (node (ref "U211") (pin "2") (pinfunction "GND_2") (pintype "passive"))
      (node (ref "U211") (pin "25") (pinfunction "EPAD_25") (pintype "passive"))
      (node (ref "U211") (pin "3") (pinfunction "GND_3") (pintype "passive"))
      (node (ref "U212") (pin "2") (pinfunction "GND_2") (pintype "passive"))
      (node (ref "U212") (pin "25") (pinfunction "EPAD_25") (pintype "passive"))
      (node (ref "U212") (pin "3") (pinfunction "GND_3") (pintype "passive"))
      (node (ref "U213") (pin "2") (pinfunction "GND_2") (pintype "passive"))
      (node (ref "U213") (pin "25") (pinfunction "EPAD_25") (pintype "passive"))
      (node (ref "U213") (pin "3") (pinfunction "GND_3") (pintype "passive"))
    )
    (net (code "16") (name "Net-(U210-EN_{slash}_~{FAULT})") (class "Default")
      (node (ref "C237") (pin "2") (pinfunction "2_2") (pintype "passive"))
      (node (ref "R270") (pin "1") (pinfunction "1_1") (pintype "passive"))
      (node (ref "U210") (pin "17") (pinfunction "EN_/_~{FAULT}_17") (pintype "passive"))
    )
    (net (code "17") (name "Net-(U210-OUTA1)") (class "Default")
      (node (ref "P210") (pin "4") (pinfunction "4_4") (pintype "passive"))
      (node (ref "U210") (pin "7") (pinfunction "OUTA1_7") (pintype "passive"))
    )
    (net (code "18") (name "Net-(U210-OUTA2)") (class "Default")
      (node (ref "P210") (pin "3") (pinfunction "3_3") (pintype "passive"))
      (node (ref "U210") (pin "8") (pinfunction "OUTA2_8") (pintype "passive"))
    )
    (net (code "19") (name "Net-(U210-OUTB1)") (class "Default")
      (node (ref "P210") (pin "1") (pinfunction "1_1") (pintype "passive"))
      (node (ref "U210") (pin "12") (pinfunction "OUTB1_12") (pintype "passive"))
    )
    (net (code "20") (name "Net-(U210-OUTB2)") (class "Default")
      (node (ref "P210") (pin "2") (pinfunction "2_2") (pintype "passive"))
      (node (ref "U210") (pin "11") (pinfunction "OUTB2_11") (pintype "passive"))
    )
    (net (code "21") (name "Net-(U210-SENSEA1)") (class "Default")
      (node (ref "R278") (pin "2") (pinfunction "2_2") (pintype "passive"))
      (node (ref "U210") (pin "4") (pinfunction "SNSA_4") (pintype "passive"))
      (node (ref "U210") (pin "5") (pinfunction "SENSEA1_5") (pintype "passive"))
      (node (ref "U210") (pin "6") (pinfunction "SENSEA2_6") (pintype "passive"))
    )
    (net (code "22") (name "Net-(U210-SENSEB1)") (class "Default")
      (node (ref "R277") (pin "2") (pinfunction "2_2") (pintype "passive"))
      (node (ref "U210") (pin "13") (pinfunction "SENSEB2_13") (pintype "passive"))
      (node (ref "U210") (pin "14") (pinfunction "SENSEB1_14") (pintype "passive"))
      (node (ref "U210") (pin "15") (pinfunction "SNSB_15") (pintype "passive"))
    )
    (net (code "23") (name "Net-(U210-TOFF)") (class "Default")
      (node (ref "R276") (pin "2") (pinfunction "2_2") (pintype "passive"))
      (node (ref "U210") (pin "24") (pinfunction "TOFF_24") (pintype "passive"))
    )
    (net (code "24") (name "Net-(U210-~{STBY}_{slash}_~{RESET})") (class "Default")
      (node (ref "C235") (pin "2") (pinfunction "2_2") (pintype "passive"))
      (node (ref "R268") (pin "1") (pinfunction "1_1") (pintype "passive"))
      (node (ref "U210") (pin "16") (pinfunction "~{STBY}_/_~{RESET}_16") (pintype "passive"))
    )
    (net (code "25") (name "Net-(U211-EN_{slash}_~{FAULT})") (class "Default")
      (node (ref "C238") (pin "2") (pinfunction "2_2") (pintype "passive"))
      (node (ref "R271") (pin "1") (pinfunction "1_1") (pintype "passive"))
      (node (ref "U211") (pin "17") (pinfunction "EN_/_~{FAULT}_17") (pintype "passive"))
    )
    (net (code "26") (name "Net-(U211-OUTA1)") (class "Default")
      (node (ref "P211") (pin "4") (pinfunction "4_4") (pintype "passive"))
      (node (ref "U211") (pin "7") (pinfunction "OUTA1_7") (pintype "passive"))
    )
    (net (code "27") (name "Net-(U211-OUTA2)") (class "Default")
      (node (ref "P211") (pin "3") (pinfunction "3_3") (pintype "passive"))
      (node (ref "U211") (pin "8") (pinfunction "OUTA2_8") (pintype "passive"))
    )
    (net (code "28") (name "Net-(U211-OUTB1)") (class "Default")
      (node (ref "P211") (pin "1") (pinfunction "1_1") (pintype "passive"))
      (node (ref "U211") (pin "12") (pinfunction "OUTB1_12") (pintype "passive"))
    )
    (net (code "29") (name "Net-(U211-OUTB2)") (class "Default")
      (node (ref "P211") (pin "2") (pinfunction "2_2") (pintype "passive"))
      (node (ref "U211") (pin "11") (pinfunction "OUTB2_11") (pintype "passive"))
    )
    (net (code "30") (name "Net-(U211-SENSEA1)") (class "Default")
      (node (ref "R281") (pin "2") (pinfunction "2_2") (pintype "passive"))
      (node (ref "U211") (pin "4") (pinfunction "SNSA_4") (pintype "passive"))
      (node (ref "U211") (pin "5") (pinfunction "SENSEA1_5") (pintype "passive"))
      (node (ref "U211") (pin "6") (pinfunction "SENSEA2_6") (pintype "passive"))
    )
    (net (code "31") (name "Net-(U211-SENSEB1)") (class "Default")
      (node (ref "R280") (pin "2") (pinfunction "2_2") (pintype "passive"))
      (node (ref "U211") (pin "13") (pinfunction "SENSEB2_13") (pintype "passive"))
      (node (ref "U211") (pin "14") (pinfunction "SENSEB1_14") (pintype "passive"))
      (node (ref "U211") (pin "15") (pinfunction "SNSB_15") (pintype "passive"))
    )
    (net (code "32") (name "Net-(U211-TOFF)") (class "Default")
      (node (ref "R279") (pin "2") (pinfunction "2_2") (pintype "passive"))
      (node (ref "U211") (pin "24") (pinfunction "TOFF_24") (pintype "passive"))
    )
    (net (code "33") (name "Net-(U211-~{STBY}_{slash}_~{RESET})") (class "Default")
      (node (ref "C236") (pin "2") (pinfunction "2_2") (pintype "passive"))
      (node (ref "R269") (pin "1") (pinfunction "1_1") (pintype "passive"))
      (node (ref "U211") (pin "16") (pinfunction "~{STBY}_/_~{RESET}_16") (pintype "passive"))
    )
    (net (code "34") (name "Net-(U212-EN_{slash}_~{FAULT})") (class "Default")
      (node (ref "C247") (pin "2") (pinfunction "2_2") (pintype "passive"))
      (node (ref "R284") (pin "1") (pinfunction "1_1") (pintype "passive"))
      (node (ref "U212") (pin "17") (pinfunction "EN_/_~{FAULT}_17") (pintype "passive"))
    )
    (net (code "35") (name "Net-(U212-OUTA1)") (class "Default")
      (node (ref "P212") (pin "4") (pinfunction "4_4") (pintype "passive"))
      (node (ref "U212") (pin "7") (pinfunction "OUTA1_7") (pintype "passive"))
    )
    (net (code "36") (name "Net-(U212-OUTA2)") (class "Default")
      (node (ref "P212") (pin "3") (pinfunction "3_3") (pintype "passive"))
      (node (ref "U212") (pin "8") (pinfunction "OUTA2_8") (pintype "passive"))
    )
    (net (code "37") (name "Net-(U212-OUTB1)") (class "Default")
      (node (ref "P212") (pin "1") (pinfunction "1_1") (pintype "passive"))
      (node (ref "U212") (pin "12") (pinfunction "OUTB1_12") (pintype "passive"))
    )
    (net (code "38") (name "Net-(U212-OUTB2)") (class "Default")
      (node (ref "P212") (pin "2") (pinfunction "2_2") (pintype "passive"))
      (node (ref "U212") (pin "11") (pinfunction "OUTB2_11") (pintype "passive"))
    )
    (net (code "39") (name "Net-(U212-SENSEA1)") (class "Default")
      (node (ref "R292") (pin "2") (pinfunction "2_2") (pintype "passive"))
      (node (ref "U212") (pin "4") (pinfunction "SNSA_4") (pintype "passive"))
      (node (ref "U212") (pin "5") (pinfunction "SENSEA1_5") (pintype "passive"))
      (node (ref "U212") (pin "6") (pinfunction "SENSEA2_6") (pintype "passive"))
    )
    (net (code "40") (name "Net-(U212-SENSEB1)") (class "Default")
      (node (ref "R291") (pin "2") (pinfunction "2_2") (pintype "passive"))
      (node (ref "U212") (pin "13") (pinfunction "SENSEB2_13") (pintype "passive"))
      (node (ref "U212") (pin "14") (pinfunction "SENSEB1_14") (pintype "passive"))
      (node (ref "U212") (pin "15") (pinfunction "SNSB_15") (pintype "passive"))
    )
    (net (code "41") (name "Net-(U212-TOFF)") (class "Default")
      (node (ref "R290") (pin "2") (pinfunction "2_2") (pintype "passive"))
      (node (ref "U212") (pin "24") (pinfunction "TOFF_24") (pintype "passive"))
    )
    (net (code "42") (name "Net-(U212-~{STBY}_{slash}_~{RESET})") (class "Default")
      (node (ref "C245") (pin "2") (pinfunction "2_2") (pintype "passive"))
      (node (ref "R282") (pin "1") (pinfunction "1_1") (pintype "passive"))
      (node (ref "U212") (pin "16") (pinfunction "~{STBY}_/_~{RESET}_16") (pintype "passive"))
    )
    (net (code "43") (name "Net-(U213-EN_{slash}_~{FAULT})") (class "Default")
      (node (ref "C248") (pin "2") (pinfunction "2_2") (pintype "passive"))
      (node (ref "R285") (pin "1") (pinfunction "1_1") (pintype "passive"))
      (node (ref "U213") (pin "17") (pinfunction "EN_/_~{FAULT}_17") (pintype "passive"))
    )
    (net (code "44") (name "Net-(U213-OUTA1)") (class "Default")
      (node (ref "P213") (pin "4") (pinfunction "4_4") (pintype "passive"))
      (node (ref "U213") (pin "7") (pinfunction "OUTA1_7") (pintype "passive"))
    )
    (net (code "45") (name "Net-(U213-OUTA2)") (class "Default")
      (node (ref "P213") (pin "3") (pinfunction "3_3") (pintype "passive"))
      (node (ref "U213") (pin "8") (pinfunction "OUTA2_8") (pintype "passive"))
    )
    (net (code "46") (name "Net-(U213-OUTB1)") (class "Default")
      (node (ref "P213") (pin "1") (pinfunction "1_1") (pintype "passive"))
      (node (ref "U213") (pin "12") (pinfunction "OUTB1_12") (pintype "passive"))
    )
    (net (code "47") (name "Net-(U213-OUTB2)") (class "Default")
      (node (ref "P213") (pin "2") (pinfunction "2_2") (pintype "passive"))
      (node (ref "U213") (pin "11") (pinfunction "OUTB2_11") (pintype "passive"))
    )
    (net (code "48") (name "Net-(U213-SENSEA1)") (class "Default")
      (node (ref "R295") (pin "2") (pinfunction "2_2") (pintype "passive"))
      (node (ref "U213") (pin "4") (pinfunction "SNSA_4") (pintype "passive"))
      (node (ref "U213") (pin "5") (pinfunction "SENSEA1_5") (pintype "passive"))
      (node (ref "U213") (pin "6") (pinfunction "SENSEA2_6") (pintype "passive"))
    )
    (net (code "49") (name "Net-(U213-SENSEB1)") (class "Default")
      (node (ref "R294") (pin "2") (pinfunction "2_2") (pintype "passive"))
      (node (ref "U213") (pin "13") (pinfunction "SENSEB2_13") (pintype "passive"))
      (node (ref "U213") (pin "14") (pinfunction "SENSEB1_14") (pintype "passive"))
      (node (ref "U213") (pin "15") (pinfunction "SNSB_15") (pintype "passive"))
    )
    (net (code "50") (name "Net-(U213-TOFF)") (class "Default")
      (node (ref "R293") (pin "2") (pinfunction "2_2") (pintype "passive"))
      (node (ref "U213") (pin "24") (pinfunction "TOFF_24") (pintype "passive"))
    )
    (net (code "51") (name "Net-(U213-~{STBY}_{slash}_~{RESET})") (class "Default")
      (node (ref "C246") (pin "2") (pinfunction "2_2") (pintype "passive"))
      (node (ref "R283") (pin "1") (pinfunction "1_1") (pintype "passive"))
      (node (ref "U213") (pin "16") (pinfunction "~{STBY}_/_~{RESET}_16") (pintype "passive"))
    )
  )
)
